# power.net
KiCad netlist of a schematic drawn in Altium Designer
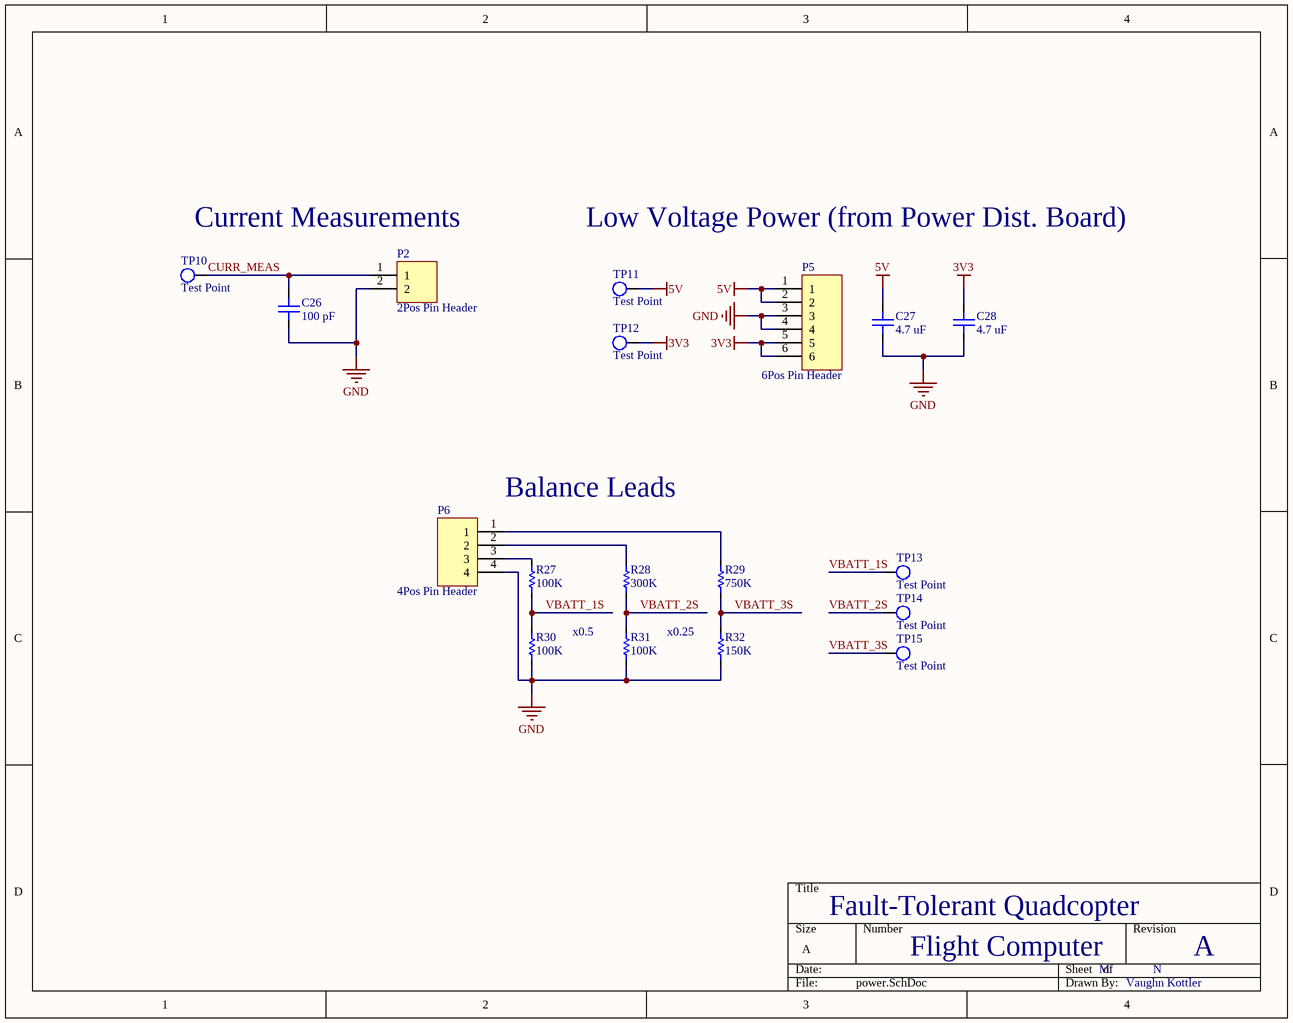
[diagram p0: power.SchDoc]

(export (version "E")
  (design (tool "Eeschema 10.0.6"))
  (components
    (comp (ref "C26")
      (value "100 pF")
      (footprint "CAP-CER-0805-SHORT")
      (description "±0.25pF, 0805")
      (libsource (lib "passive") (part "CAP-CER-100pF-50V"))
    )
    (comp (ref "C27")
      (value "4.7 uF")
      (footprint "CAP-CER-0805-TALL")
      (description "±10%, 0805")
      (libsource (lib "passive") (part "CAP-CER-4.7uF-10V"))
    )
    (comp (ref "C28")
      (value "4.7 uF")
      (footprint "CAP-CER-0805-TALL")
      (description "±10%, 0805")
      (libsource (lib "passive") (part "CAP-CER-4.7uF-10V"))
    )
    (comp (ref "P2")
      (value "2Pos Pin Header")
      (footprint "2Pos Pin Header JST")
      (description "0.1\" Pitch 1x2")
      (libsource (lib "connector") (part "2Pos Pin Header"))
    )
    (comp (ref "P5")
      (value "6Pos Pin Header")
      (footprint "6Pos Pin Header JST")
      (description "0.1\" Pitch 1x6")
      (libsource (lib "connector") (part "6Pos Pin Header"))
    )
    (comp (ref "P6")
      (value "4Pos Pin Header")
      (footprint "4Pos Pin Header JST")
      (description "0.1\" Pitch 1x4")
      (libsource (lib "connector") (part "4Pos Pin Header"))
    )
    (comp (ref "R27")
      (value "100K")
      (footprint "RES-0805")
      (description "0805")
      (libsource (lib "passive") (part "RES-100K-1/8W"))
    )
    (comp (ref "R28")
      (value "300K")
      (footprint "RES-0805")
      (description "0805")
      (libsource (lib "passive") (part "RES-300K-1/8W"))
    )
    (comp (ref "R29")
      (value "750K")
      (footprint "RES-0805")
      (description "0805")
      (libsource (lib "passive") (part "RES-750K-1/8W"))
    )
    (comp (ref "R30")
      (value "100K")
      (footprint "RES-0805")
      (description "0805")
      (libsource (lib "passive") (part "RES-100K-1/8W"))
    )
    (comp (ref "R31")
      (value "100K")
      (footprint "RES-0805")
      (description "0805")
      (libsource (lib "passive") (part "RES-100K-1/8W"))
    )
    (comp (ref "R32")
      (value "150K")
      (footprint "RES-0805")
      (description "0805")
      (libsource (lib "passive") (part "RES-150K-1/8W"))
    )
    (comp (ref "TP10")
      (value "Test Point")
      (footprint "0603 Test Point")
      (description "0603")
      (libsource (lib "passive") (part "Test Point"))
    )
    (comp (ref "TP11")
      (value "Test Point")
      (footprint "0603 Test Point")
      (description "0603")
      (libsource (lib "passive") (part "Test Point"))
    )
    (comp (ref "TP12")
      (value "Test Point")
      (footprint "0603 Test Point")
      (description "0603")
      (libsource (lib "passive") (part "Test Point"))
    )
    (comp (ref "TP13")
      (value "Test Point")
      (footprint "0603 Test Point")
      (description "0603")
      (libsource (lib "passive") (part "Test Point"))
    )
    (comp (ref "TP14")
      (value "Test Point")
      (footprint "0603 Test Point")
      (description "0603")
      (libsource (lib "passive") (part "Test Point"))
    )
    (comp (ref "TP15")
      (value "Test Point")
      (footprint "0603 Test Point")
      (description "0603")
      (libsource (lib "passive") (part "Test Point"))
    )
  )
  (nets
    (net (code "1") (name "/CURR_MEAS") (class "Default")
      (node (ref "C26") (pin "2") (pinfunction "2_2") (pintype "passive"))
      (node (ref "P2") (pin "1") (pinfunction "1_1") (pintype "passive"))
      (node (ref "TP10") (pin "1") (pinfunction "1_1") (pintype "passive"))
    )
    (net (code "2") (name "/VBATT_1S") (class "Default")
      (node (ref "R27") (pin "1") (pinfunction "1_1") (pintype "passive"))
      (node (ref "R30") (pin "2") (pinfunction "2_2") (pintype "passive"))
      (node (ref "TP13") (pin "1") (pinfunction "1_1") (pintype "passive"))
    )
    (net (code "3") (name "/VBATT_2S") (class "Default")
      (node (ref "R28") (pin "1") (pinfunction "1_1") (pintype "passive"))
      (node (ref "R31") (pin "2") (pinfunction "2_2") (pintype "passive"))
      (node (ref "TP14") (pin "1") (pinfunction "1_1") (pintype "passive"))
    )
    (net (code "4") (name "/VBATT_3S") (class "Default")
      (node (ref "R29") (pin "1") (pinfunction "1_1") (pintype "passive"))
      (node (ref "R32") (pin "2") (pinfunction "2_2") (pintype "passive"))
      (node (ref "TP15") (pin "1") (pinfunction "1_1") (pintype "passive"))
    )
    (net (code "5") (name "3V3") (class "Default")
      (node (ref "C28") (pin "2") (pinfunction "2_2") (pintype "passive"))
      (node (ref "P5") (pin "5") (pinfunction "5_5") (pintype "passive"))
      (node (ref "P5") (pin "6") (pinfunction "6_6") (pintype "passive"))
      (node (ref "TP12") (pin "1") (pinfunction "1_1") (pintype "passive"))
    )
    (net (code "6") (name "5V") (class "Default")
      (node (ref "C27") (pin "2") (pinfunction "2_2") (pintype "passive"))
      (node (ref "P5") (pin "1") (pinfunction "1_1") (pintype "passive"))
      (node (ref "P5") (pin "2") (pinfunction "2_2") (pintype "passive"))
      (node (ref "TP11") (pin "1") (pinfunction "1_1") (pintype "passive"))
    )
    (net (code "7") (name "GND") (class "Default")
      (node (ref "C26") (pin "1") (pinfunction "1_1") (pintype "passive"))
      (node (ref "C27") (pin "1") (pinfunction "1_1") (pintype "passive"))
      (node (ref "C28") (pin "1") (pinfunction "1_1") (pintype "passive"))
      (node (ref "P2") (pin "2") (pinfunction "2_2") (pintype "passive"))
      (node (ref "P5") (pin "3") (pinfunction "3_3") (pintype "passive"))
      (node (ref "P5") (pin "4") (pinfunction "4_4") (pintype "passive"))
      (node (ref "P6") (pin "4") (pinfunction "4_4") (pintype "passive"))
      (node (ref "R30") (pin "1") (pinfunction "1_1") (pintype "passive"))
      (node (ref "R31") (pin "1") (pinfunction "1_1") (pintype "passive"))
      (node (ref "R32") (pin "1") (pinfunction "1_1") (pintype "passive"))
    )
    (net (code "8") (name "Net-(P6-Pad1)") (class "Default")
      (node (ref "P6") (pin "1") (pinfunction "1_1") (pintype "passive"))
      (node (ref "R29") (pin "2") (pinfunction "2_2") (pintype "passive"))
    )
    (net (code "9") (name "Net-(P6-Pad2)") (class "Default")
      (node (ref "P6") (pin "2") (pinfunction "2_2") (pintype "passive"))
      (node (ref "R28") (pin "2") (pinfunction "2_2") (pintype "passive"))
    )
    (net (code "10") (name "Net-(P6-Pad3)") (class "Default")
      (node (ref "P6") (pin "3") (pinfunction "3_3") (pintype "passive"))
      (node (ref "R27") (pin "2") (pinfunction "2_2") (pintype "passive"))
    )
  )
)
